# WIFI.net
KiCad netlist of a schematic drawn in Altium Designer
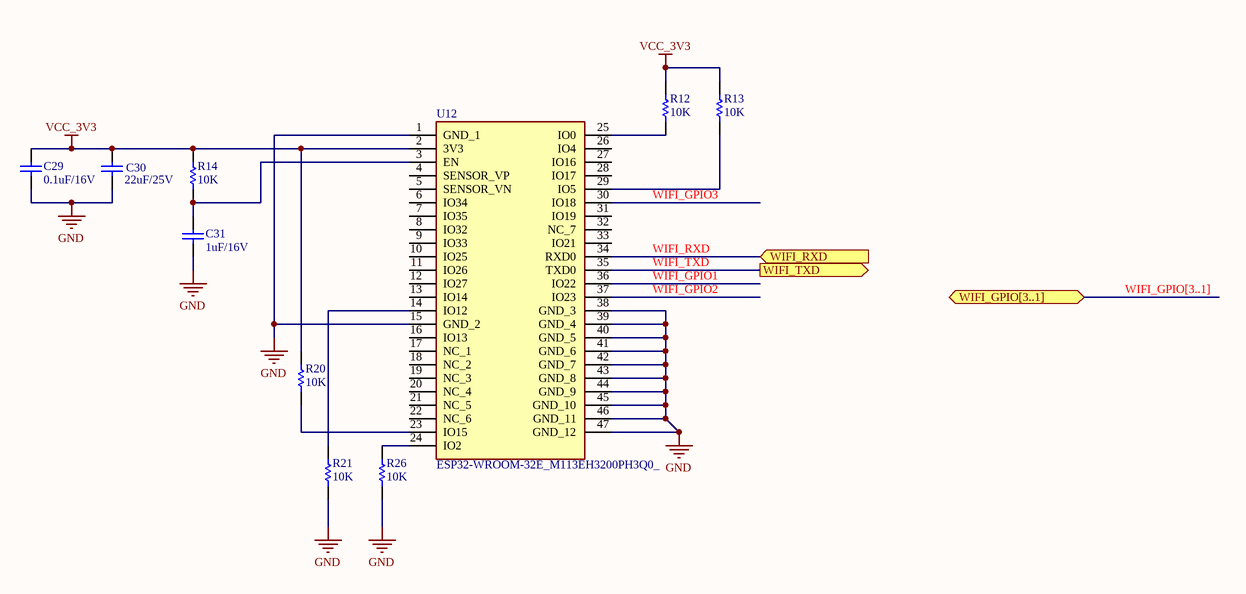
[diagram p0: WIFI.SchDoc]

(export (version "E")
  (design (tool "Eeschema 10.0.6"))
  (components
    (comp (ref "C29")
      (value "0.1uF/16V")
      (footprint "0603C")
      (description "Multilayer Ceramic Capacitors MLCC - SMD/SMT 0603 16VDC 0.1uF 10% X7R AEC-Q2000")
      (fields (field (name "MFR") "Taiyo Yuden") (field (name "MFR PART NO") "EMK107B7104KAHT"))
      (libsource (lib "Miscellaneous Devices") (part "Cap"))
    )
    (comp (ref "C30")
      (value "22uF/25V")
      (footprint "1210C")
      (description "Multilayer Ceramic Capacitors MLCC - SMD/SMT 1210 25VDC 22uF 20% X7R AEC-Q200")
      (fields (field (name "MFR") "Taiyo Yuden") (field (name "MFR PART NO") "TMK325B7226MMHP"))
      (libsource (lib "Miscellaneous Devices") (part "Cap"))
    )
    (comp (ref "C31")
      (value "1uF/16V")
      (footprint "0603C")
      (description "Multilayer Ceramic Capacitors MLCC - SMD/SMT 16volts 1uF X7R 10%")
      (fields (field (name "MFR") "KEMET") (field (name "MFR PART NO") "C0603C105K4RAC7411"))
      (libsource (lib "Miscellaneous Devices") (part "Cap"))
    )
    (comp (ref "R12")
      (value "10K")
      (footprint "0603R")
      (description "Thick Film Resistors - SMD 0603 10Kohms 1% Anti-Sulfur AEC-Q200")
      (fields (field (name "MFR") "ROHM Semiconductor") (field (name "MFR PART NO") "SFR03EZPF1002"))
      (libsource (lib "Miscellaneous Devices") (part "Res1"))
    )
    (comp (ref "R13")
      (value "10K")
      (footprint "0603R")
      (description "Thick Film Resistors - SMD 0603 10Kohms 1% Anti-Sulfur AEC-Q200")
      (fields (field (name "MFR") "ROHM Semiconductor") (field (name "MFR PART NO") "SFR03EZPF1002"))
      (libsource (lib "Miscellaneous Devices") (part "Res1"))
    )
    (comp (ref "R14")
      (value "10K")
      (footprint "0603R")
      (description "Thick Film Resistors - SMD 0603 10Kohms 1% Anti-Sulfur AEC-Q200")
      (fields (field (name "MFR") "ROHM Semiconductor") (field (name "MFR PART NO") "SFR03EZPF1002"))
      (libsource (lib "Miscellaneous Devices") (part "Res1"))
    )
    (comp (ref "R20")
      (value "10K")
      (footprint "0603R")
      (description "Thick Film Resistors - SMD 0603 10Kohms 1% Anti-Sulfur AEC-Q200")
      (fields (field (name "MFR") "ROHM Semiconductor") (field (name "MFR PART NO") "SFR03EZPF1002"))
      (libsource (lib "Miscellaneous Devices") (part "Res1"))
    )
    (comp (ref "R21")
      (value "10K")
      (footprint "0603R")
      (description "Thick Film Resistors - SMD 0603 10Kohms 1% Anti-Sulfur AEC-Q200")
      (fields (field (name "MFR") "ROHM Semiconductor") (field (name "MFR PART NO") "SFR03EZPF1002"))
      (libsource (lib "Miscellaneous Devices") (part "Res1"))
    )
    (comp (ref "R26")
      (value "10K")
      (footprint "0603R")
      (description "Thick Film Resistors - SMD 0603 10Kohms 1% Anti-Sulfur AEC-Q200")
      (fields (field (name "MFR") "ROHM Semiconductor") (field (name "MFR PART NO") "SFR03EZPF1002"))
      (libsource (lib "Miscellaneous Devices") (part "Res1"))
    )
    (comp (ref "U12")
      (value "ESP32-WROOM-32E_M113EH3200PH3Q0_")
      (footprint "ESP32WROOM32EM113EH3200PH3Q0")
      (description "Integrated Circuit")
      (fields
        (field (name "MFR") "Espressif Systems")
        (field (name "MFR PART NO") "ESP32-WROOM-32E(M113EH3200PH3Q0)")
      )
      (libsource (lib "*") (part "ESP32-WROOM-32E_M113EH3200PH3Q0_"))
    )
  )
  (nets
    (net (code "1") (name "/WIFI_GPIO1") (class "Default")
      (node (ref "U12") (pin "36") (pinfunction "IO22_36") (pintype "passive"))
    )
    (net (code "2") (name "/WIFI_GPIO2") (class "Default")
      (node (ref "U12") (pin "37") (pinfunction "IO23_37") (pintype "passive"))
    )
    (net (code "3") (name "/WIFI_GPIO3") (class "Default")
      (node (ref "U12") (pin "30") (pinfunction "IO18_30") (pintype "passive"))
    )
    (net (code "5") (name "/WIFI_RXD") (class "Default")
      (node (ref "U12") (pin "34") (pinfunction "RXD0_34") (pintype "passive"))
    )
    (net (code "6") (name "/WIFI_TXD") (class "Default")
      (node (ref "U12") (pin "35") (pinfunction "TXD0_35") (pintype "passive"))
    )
    (net (code "7") (name "GND") (class "Default")
      (node (ref "C29") (pin "2") (pinfunction "2_2") (pintype "passive"))
      (node (ref "C30") (pin "1") (pinfunction "1_1") (pintype "passive"))
      (node (ref "C31") (pin "2") (pinfunction "2_2") (pintype "passive"))
      (node (ref "R21") (pin "2") (pinfunction "2_2") (pintype "passive"))
      (node (ref "R26") (pin "2") (pinfunction "2_2") (pintype "passive"))
      (node (ref "U12") (pin "1") (pinfunction "GND_1_1") (pintype "passive"))
      (node (ref "U12") (pin "15") (pinfunction "GND_2_15") (pintype "passive"))
      (node (ref "U12") (pin "38") (pinfunction "GND_3_38") (pintype "passive"))
      (node (ref "U12") (pin "39") (pinfunction "GND_4_39") (pintype "passive"))
      (node (ref "U12") (pin "40") (pinfunction "GND_5_40") (pintype "passive"))
      (node (ref "U12") (pin "41") (pinfunction "GND_6_41") (pintype "passive"))
      (node (ref "U12") (pin "42") (pinfunction "GND_7_42") (pintype "passive"))
      (node (ref "U12") (pin "43") (pinfunction "GND_8_43") (pintype "passive"))
      (node (ref "U12") (pin "44") (pinfunction "GND_9_44") (pintype "passive"))
      (node (ref "U12") (pin "45") (pinfunction "GND_10_45") (pintype "passive"))
      (node (ref "U12") (pin "46") (pinfunction "GND_11_46") (pintype "passive"))
      (node (ref "U12") (pin "47") (pinfunction "GND_12_47") (pintype "passive"))
    )
    (net (code "8") (name "Net-(U12-EN)") (class "Default")
      (node (ref "C31") (pin "1") (pinfunction "1_1") (pintype "passive"))
      (node (ref "R14") (pin "2") (pinfunction "2_2") (pintype "passive"))
      (node (ref "U12") (pin "3") (pinfunction "EN_3") (pintype "passive"))
    )
    (net (code "9") (name "Net-(U12-IO0)") (class "Default")
      (node (ref "R12") (pin "2") (pinfunction "2_2") (pintype "passive"))
      (node (ref "U12") (pin "25") (pinfunction "IO0_25") (pintype "passive"))
    )
    (net (code "10") (name "Net-(U12-IO2)") (class "Default")
      (node (ref "R26") (pin "1") (pinfunction "1_1") (pintype "passive"))
      (node (ref "U12") (pin "24") (pinfunction "IO2_24") (pintype "passive"))
    )
    (net (code "11") (name "Net-(U12-IO5)") (class "Default")
      (node (ref "R13") (pin "2") (pinfunction "2_2") (pintype "passive"))
      (node (ref "U12") (pin "29") (pinfunction "IO5_29") (pintype "passive"))
    )
    (net (code "12") (name "Net-(U12-IO12)") (class "Default")
      (node (ref "R21") (pin "1") (pinfunction "1_1") (pintype "passive"))
      (node (ref "U12") (pin "14") (pinfunction "IO12_14") (pintype "passive"))
    )
    (net (code "13") (name "Net-(U12-IO15)") (class "Default")
      (node (ref "R20") (pin "2") (pinfunction "2_2") (pintype "passive"))
      (node (ref "U12") (pin "23") (pinfunction "IO15_23") (pintype "passive"))
    )
    (net (code "14") (name "VCC_3V3") (class "Default")
      (node (ref "C29") (pin "1") (pinfunction "1_1") (pintype "passive"))
      (node (ref "C30") (pin "2") (pinfunction "2_2") (pintype "passive"))
      (node (ref "R12") (pin "1") (pinfunction "1_1") (pintype "passive"))
      (node (ref "R13") (pin "1") (pinfunction "1_1") (pintype "passive"))
      (node (ref "R14") (pin "1") (pinfunction "1_1") (pintype "passive"))
      (node (ref "R20") (pin "1") (pinfunction "1_1") (pintype "passive"))
      (node (ref "U12") (pin "2") (pinfunction "3V3_2") (pintype "passive"))
    )
    (net (code "15") (name "unconnected-(U12-IO4-Pad26)") (class "Default")
      (node (ref "U12") (pin "26") (pinfunction "IO4_26") (pintype "passive"))
    )
    (net (code "16") (name "unconnected-(U12-IO13-Pad16)") (class "Default")
      (node (ref "U12") (pin "16") (pinfunction "IO13_16") (pintype "passive"))
    )
    (net (code "17") (name "unconnected-(U12-IO14-Pad13)") (class "Default")
      (node (ref "U12") (pin "13") (pinfunction "IO14_13") (pintype "passive"))
    )
    (net (code "18") (name "unconnected-(U12-IO16-Pad27)") (class "Default")
      (node (ref "U12") (pin "27") (pinfunction "IO16_27") (pintype "passive"))
    )
    (net (code "19") (name "unconnected-(U12-IO17-Pad28)") (class "Default")
      (node (ref "U12") (pin "28") (pinfunction "IO17_28") (pintype "passive"))
    )
    (net (code "20") (name "unconnected-(U12-IO19-Pad31)") (class "Default")
      (node (ref "U12") (pin "31") (pinfunction "IO19_31") (pintype "passive"))
    )
    (net (code "21") (name "unconnected-(U12-IO21-Pad33)") (class "Default")
      (node (ref "U12") (pin "33") (pinfunction "IO21_33") (pintype "passive"))
    )
    (net (code "22") (name "unconnected-(U12-IO25-Pad10)") (class "Default")
      (node (ref "U12") (pin "10") (pinfunction "IO25_10") (pintype "passive"))
    )
    (net (code "23") (name "unconnected-(U12-IO26-Pad11)") (class "Default")
      (node (ref "U12") (pin "11") (pinfunction "IO26_11") (pintype "passive"))
    )
    (net (code "24") (name "unconnected-(U12-IO27-Pad12)") (class "Default")
      (node (ref "U12") (pin "12") (pinfunction "IO27_12") (pintype "passive"))
    )
    (net (code "25") (name "unconnected-(U12-IO32-Pad8)") (class "Default")
      (node (ref "U12") (pin "8") (pinfunction "IO32_8") (pintype "passive"))
    )
    (net (code "26") (name "unconnected-(U12-IO33-Pad9)") (class "Default")
      (node (ref "U12") (pin "9") (pinfunction "IO33_9") (pintype "passive"))
    )
    (net (code "27") (name "unconnected-(U12-IO34-Pad6)") (class "Default")
      (node (ref "U12") (pin "6") (pinfunction "IO34_6") (pintype "passive"))
    )
    (net (code "28") (name "unconnected-(U12-IO35-Pad7)") (class "Default")
      (node (ref "U12") (pin "7") (pinfunction "IO35_7") (pintype "passive"))
    )
    (net (code "29") (name "unconnected-(U12-NC_1-Pad17)") (class "Default")
      (node (ref "U12") (pin "17") (pinfunction "NC_1_17") (pintype "passive"))
    )
    (net (code "30") (name "unconnected-(U12-NC_2-Pad18)") (class "Default")
      (node (ref "U12") (pin "18") (pinfunction "NC_2_18") (pintype "passive"))
    )
    (net (code "31") (name "unconnected-(U12-NC_3-Pad19)") (class "Default")
      (node (ref "U12") (pin "19") (pinfunction "NC_3_19") (pintype "passive"))
    )
    (net (code "32") (name "unconnected-(U12-NC_4-Pad20)") (class "Default")
      (node (ref "U12") (pin "20") (pinfunction "NC_4_20") (pintype "passive"))
    )
    (net (code "33") (name "unconnected-(U12-NC_5-Pad21)") (class "Default")
      (node (ref "U12") (pin "21") (pinfunction "NC_5_21") (pintype "passive"))
    )
    (net (code "34") (name "unconnected-(U12-NC_6-Pad22)") (class "Default")
      (node (ref "U12") (pin "22") (pinfunction "NC_6_22") (pintype "passive"))
    )
    (net (code "35") (name "unconnected-(U12-NC_7-Pad32)") (class "Default")
      (node (ref "U12") (pin "32") (pinfunction "NC_7_32") (pintype "passive"))
    )
    (net (code "36") (name "unconnected-(U12-SENSOR_VN-Pad5)") (class "Default")
      (node (ref "U12") (pin "5") (pinfunction "SENSOR_VN_5") (pintype "passive"))
    )
    (net (code "37") (name "unconnected-(U12-SENSOR_VP-Pad4)") (class "Default")
      (node (ref "U12") (pin "4") (pinfunction "SENSOR_VP_4") (pintype "passive"))
    )
  )
)
